# witch-dekatron1.net
KiCad netlist of a schematic drawn in EAGLE
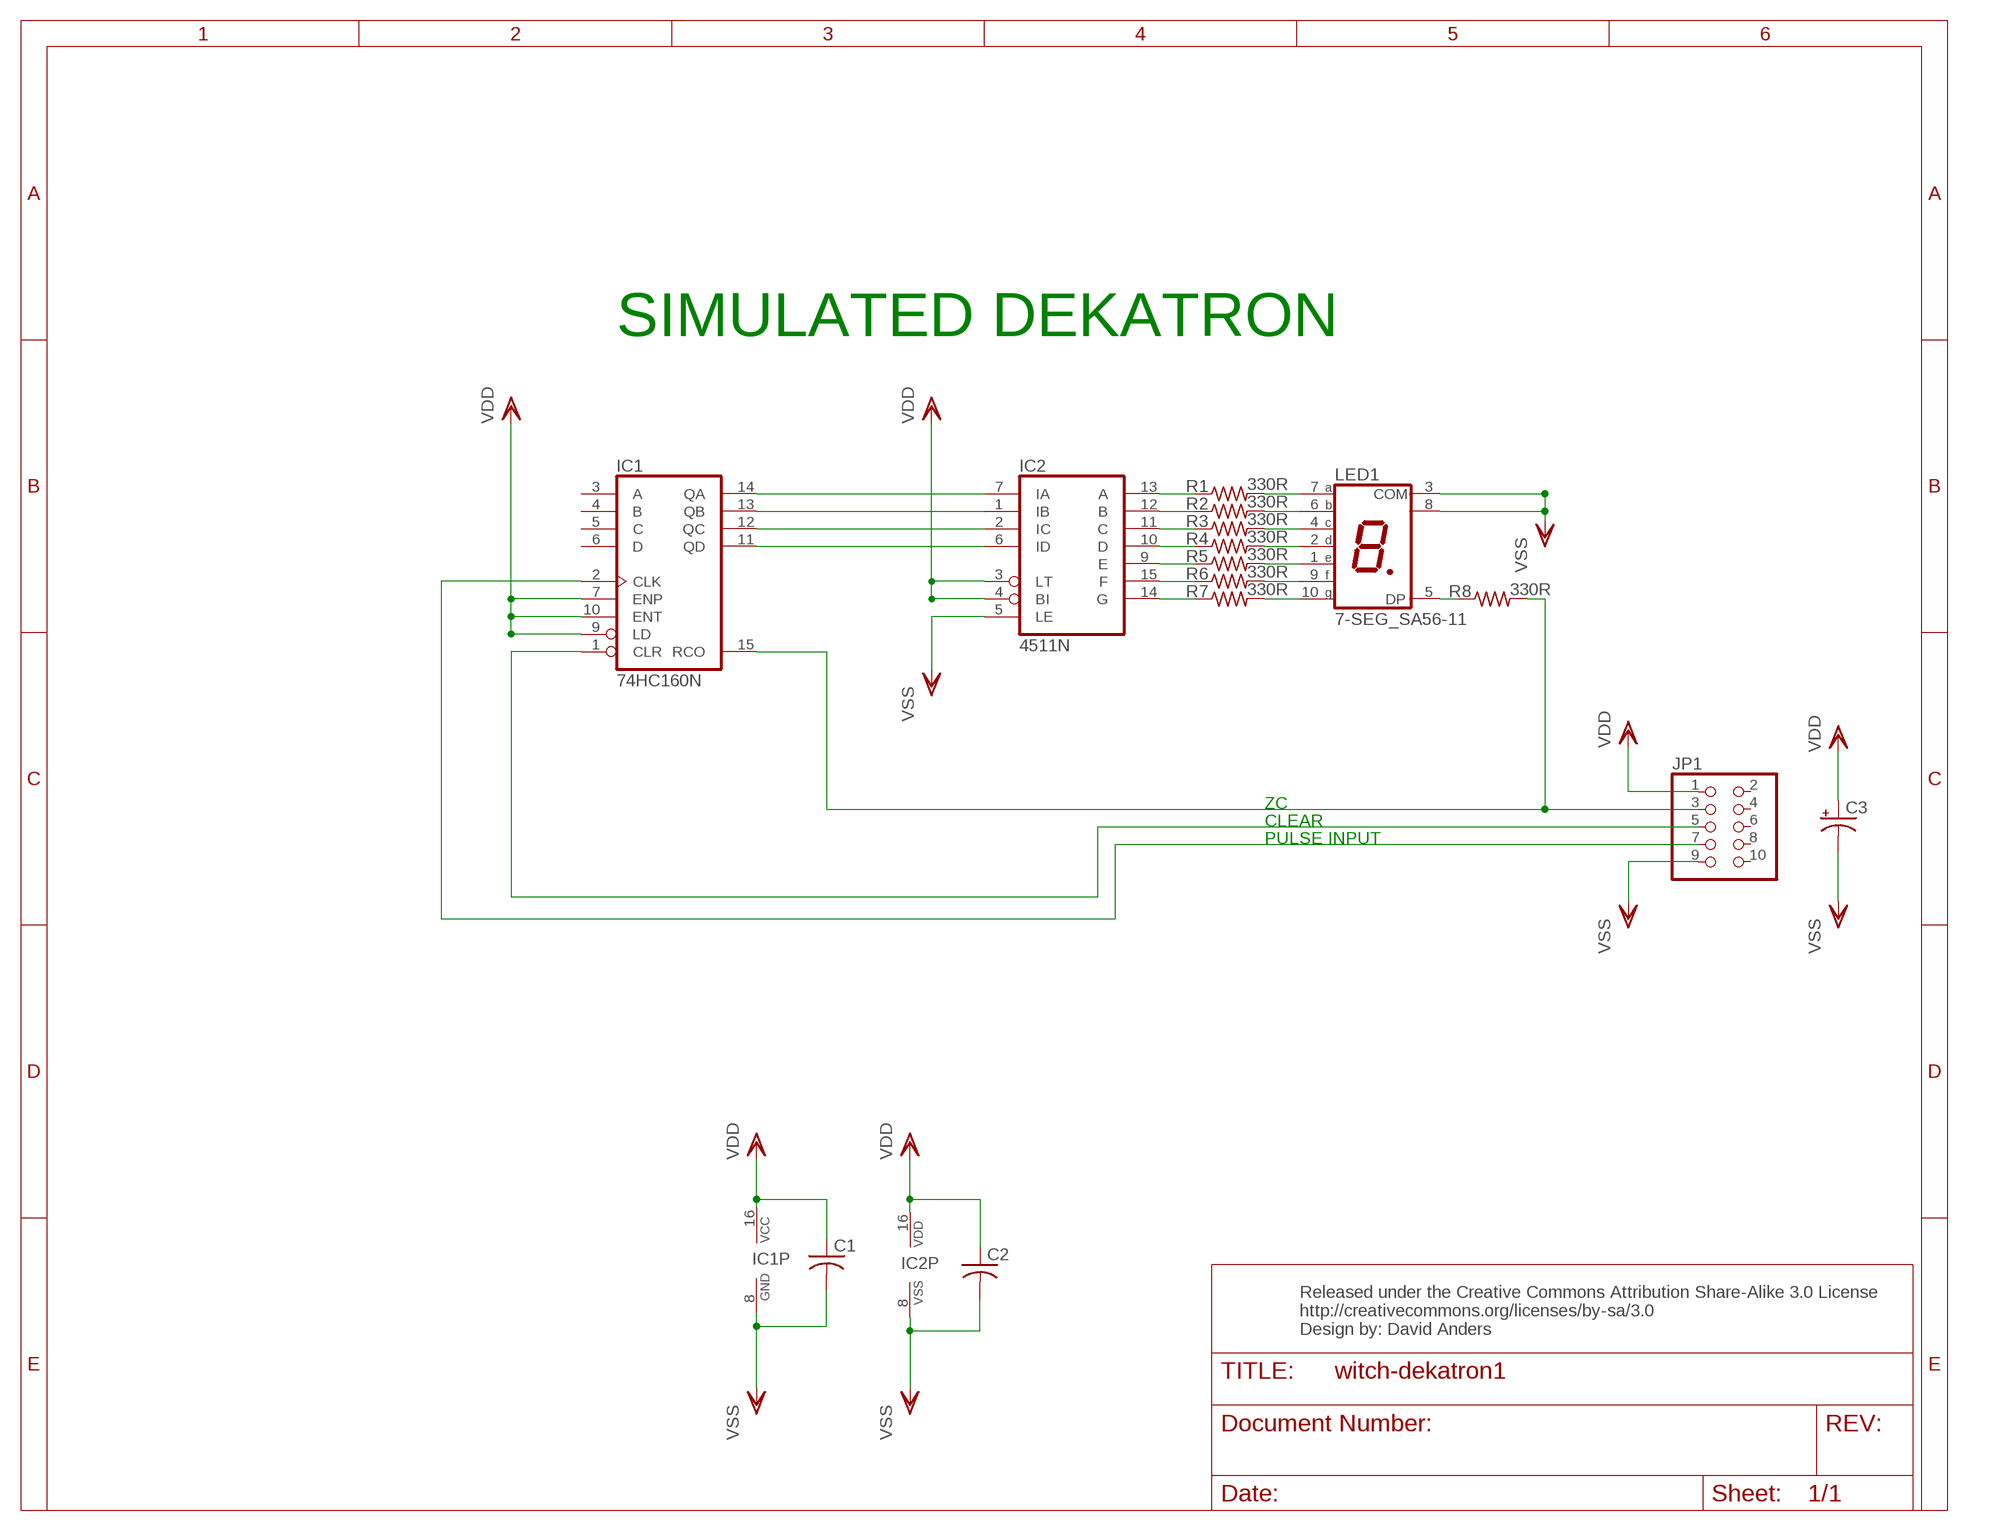
[diagram p0: schematic, sheet 1]

(export (version "E")
  (design (tool "Eeschema 10.0.6"))
  (components
    (comp (ref "C1")
      (value "C-US025-025X050")
      (footprint "eagle-import:C025-025X050")
      (libsource (lib "eagle-import") (part "C-US025-025X050"))
    )
    (comp (ref "C2")
      (value "C-US025-025X050")
      (footprint "eagle-import:C025-025X050")
      (libsource (lib "eagle-import") (part "C-US025-025X050"))
    )
    (comp (ref "C3")
      (value "CPOL-USE2-5")
      (footprint "eagle-import:E2-5")
      (libsource (lib "eagle-import") (part "CPOL-USE2-5"))
    )
    (comp (ref "IC1")
      (value "74HC160N")
      (footprint "eagle-import:DIL16")
      (libsource (lib "eagle-import") (part "74160NHC"))
    )
    (comp (ref "IC2")
      (value "4511N")
      (footprint "eagle-import:DIL16")
      (libsource (lib "eagle-import") (part "4511N"))
    )
    (comp (ref "JP1")
      (value "PINHD-2X5")
      (footprint "eagle-import:2X05")
      (libsource (lib "eagle-import") (part "PINHD-2X5"))
    )
    (comp (ref "LED1")
      (value "7-SEG_SA56-11")
      (footprint "eagle-import:SA56-11")
      (libsource (lib "eagle-import") (part "7-SEG_SA56-11"))
    )
    (comp (ref "R1")
      (value "330R")
      (footprint "eagle-import:0204_5")
      (libsource (lib "eagle-import") (part "R-US_0204/5"))
    )
    (comp (ref "R2")
      (value "330R")
      (footprint "eagle-import:0204_5")
      (libsource (lib "eagle-import") (part "R-US_0204/5"))
    )
    (comp (ref "R3")
      (value "330R")
      (footprint "eagle-import:0204_5")
      (libsource (lib "eagle-import") (part "R-US_0204/5"))
    )
    (comp (ref "R4")
      (value "330R")
      (footprint "eagle-import:0204_5")
      (libsource (lib "eagle-import") (part "R-US_0204/5"))
    )
    (comp (ref "R5")
      (value "330R")
      (footprint "eagle-import:0204_5")
      (libsource (lib "eagle-import") (part "R-US_0204/5"))
    )
    (comp (ref "R6")
      (value "330R")
      (footprint "eagle-import:0204_5")
      (libsource (lib "eagle-import") (part "R-US_0204/5"))
    )
    (comp (ref "R7")
      (value "330R")
      (footprint "eagle-import:0204_5")
      (libsource (lib "eagle-import") (part "R-US_0204/5"))
    )
    (comp (ref "R8")
      (value "330R")
      (footprint "eagle-import:0204_5")
      (libsource (lib "eagle-import") (part "R-US_0204/5"))
    )
  )
  (nets
    (net (code "1") (name "Net-(IC1A-CLK)") (class "Default")
      (node (ref "IC1") (pin "2") (pinfunction "CLK_2") (pintype "input"))
      (node (ref "JP1") (pin "7") (pinfunction "7_7") (pintype "passive"))
    )
    (net (code "2") (name "Net-(IC1A-CLR)") (class "Default")
      (node (ref "IC1") (pin "1") (pinfunction "CLR_1") (pintype "input"))
      (node (ref "JP1") (pin "5") (pinfunction "5_5") (pintype "passive"))
    )
    (net (code "3") (name "Net-(IC1A-QA)") (class "Default")
      (node (ref "IC1") (pin "14") (pinfunction "QA_14") (pintype "output"))
      (node (ref "IC2") (pin "7") (pinfunction "IA_7") (pintype "input"))
    )
    (net (code "4") (name "Net-(IC1A-QB)") (class "Default")
      (node (ref "IC1") (pin "13") (pinfunction "QB_13") (pintype "output"))
      (node (ref "IC2") (pin "1") (pinfunction "IB_1") (pintype "input"))
    )
    (net (code "5") (name "Net-(IC1A-QC)") (class "Default")
      (node (ref "IC1") (pin "12") (pinfunction "QC_12") (pintype "output"))
      (node (ref "IC2") (pin "2") (pinfunction "IC_2") (pintype "input"))
    )
    (net (code "6") (name "Net-(IC1A-QD)") (class "Default")
      (node (ref "IC1") (pin "11") (pinfunction "QD_11") (pintype "output"))
      (node (ref "IC2") (pin "6") (pinfunction "ID_6") (pintype "input"))
    )
    (net (code "7") (name "Net-(IC1A-RCO)") (class "Default")
      (node (ref "IC1") (pin "15") (pinfunction "RCO_15") (pintype "output"))
      (node (ref "JP1") (pin "3") (pinfunction "3_3") (pintype "passive"))
      (node (ref "R8") (pin "2") (pinfunction "2_2") (pintype "passive"))
    )
    (net (code "8") (name "Net-(IC2A-A)") (class "Default")
      (node (ref "IC2") (pin "13") (pinfunction "A_13") (pintype "output"))
      (node (ref "R1") (pin "1") (pinfunction "1_1") (pintype "passive"))
    )
    (net (code "9") (name "Net-(IC2A-B)") (class "Default")
      (node (ref "IC2") (pin "12") (pinfunction "B_12") (pintype "output"))
      (node (ref "R2") (pin "1") (pinfunction "1_1") (pintype "passive"))
    )
    (net (code "10") (name "Net-(IC2A-C)") (class "Default")
      (node (ref "IC2") (pin "11") (pinfunction "C_11") (pintype "output"))
      (node (ref "R3") (pin "1") (pinfunction "1_1") (pintype "passive"))
    )
    (net (code "11") (name "Net-(IC2A-D)") (class "Default")
      (node (ref "IC2") (pin "10") (pinfunction "D_10") (pintype "output"))
      (node (ref "R4") (pin "1") (pinfunction "1_1") (pintype "passive"))
    )
    (net (code "12") (name "Net-(IC2A-E)") (class "Default")
      (node (ref "IC2") (pin "9") (pinfunction "E_9") (pintype "output"))
      (node (ref "R5") (pin "1") (pinfunction "1_1") (pintype "passive"))
    )
    (net (code "13") (name "Net-(IC2A-F)") (class "Default")
      (node (ref "IC2") (pin "15") (pinfunction "F_15") (pintype "output"))
      (node (ref "R6") (pin "1") (pinfunction "1_1") (pintype "passive"))
    )
    (net (code "14") (name "Net-(IC2A-G)") (class "Default")
      (node (ref "IC2") (pin "14") (pinfunction "G_14") (pintype "output"))
      (node (ref "R7") (pin "1") (pinfunction "1_1") (pintype "passive"))
    )
    (net (code "15") (name "Net-(LED1-A)") (class "Default")
      (node (ref "LED1") (pin "7") (pinfunction "A_7") (pintype "passive"))
      (node (ref "R1") (pin "2") (pinfunction "2_2") (pintype "passive"))
    )
    (net (code "16") (name "Net-(LED1-B)") (class "Default")
      (node (ref "LED1") (pin "6") (pinfunction "B_6") (pintype "passive"))
      (node (ref "R2") (pin "2") (pinfunction "2_2") (pintype "passive"))
    )
    (net (code "17") (name "Net-(LED1-C)") (class "Default")
      (node (ref "LED1") (pin "4") (pinfunction "C_4") (pintype "passive"))
      (node (ref "R3") (pin "2") (pinfunction "2_2") (pintype "passive"))
    )
    (net (code "18") (name "Net-(LED1-D)") (class "Default")
      (node (ref "LED1") (pin "2") (pinfunction "D_2") (pintype "passive"))
      (node (ref "R4") (pin "2") (pinfunction "2_2") (pintype "passive"))
    )
    (net (code "19") (name "Net-(LED1-DP)") (class "Default")
      (node (ref "LED1") (pin "5") (pinfunction "DP_5") (pintype "passive"))
      (node (ref "R8") (pin "1") (pinfunction "1_1") (pintype "passive"))
    )
    (net (code "20") (name "Net-(LED1-E)") (class "Default")
      (node (ref "LED1") (pin "1") (pinfunction "E_1") (pintype "passive"))
      (node (ref "R5") (pin "2") (pinfunction "2_2") (pintype "passive"))
    )
    (net (code "21") (name "Net-(LED1-F)") (class "Default")
      (node (ref "LED1") (pin "9") (pinfunction "F_9") (pintype "passive"))
      (node (ref "R6") (pin "2") (pinfunction "2_2") (pintype "passive"))
    )
    (net (code "22") (name "Net-(LED1-G)") (class "Default")
      (node (ref "LED1") (pin "10") (pinfunction "G_10") (pintype "passive"))
      (node (ref "R7") (pin "2") (pinfunction "2_2") (pintype "passive"))
    )
    (net (code "23") (name "VDD") (class "Default")
      (node (ref "C1") (pin "1") (pinfunction "1_1") (pintype "passive"))
      (node (ref "C2") (pin "1") (pinfunction "1_1") (pintype "passive"))
      (node (ref "C3") (pin "+") (pinfunction "+_+") (pintype "passive"))
      (node (ref "IC1") (pin "10") (pinfunction "ENT_10") (pintype "input"))
      (node (ref "IC1") (pin "16") (pinfunction "VCC_16") (pintype "power_in"))
      (node (ref "IC1") (pin "7") (pinfunction "ENP_7") (pintype "input"))
      (node (ref "IC1") (pin "9") (pinfunction "LD_9") (pintype "input"))
      (node (ref "IC2") (pin "16") (pinfunction "VDD_16") (pintype "power_in"))
      (node (ref "IC2") (pin "3") (pinfunction "LT_3") (pintype "input"))
      (node (ref "IC2") (pin "4") (pinfunction "BI_4") (pintype "input"))
      (node (ref "JP1") (pin "1") (pinfunction "1_1") (pintype "passive"))
    )
    (net (code "24") (name "VSS") (class "Default")
      (node (ref "C1") (pin "2") (pinfunction "2_2") (pintype "passive"))
      (node (ref "C2") (pin "2") (pinfunction "2_2") (pintype "passive"))
      (node (ref "C3") (pin "-") (pinfunction "-_-") (pintype "passive"))
      (node (ref "IC1") (pin "8") (pinfunction "GND_8") (pintype "power_in"))
      (node (ref "IC2") (pin "5") (pinfunction "LE_5") (pintype "input"))
      (node (ref "IC2") (pin "8") (pinfunction "VSS_8") (pintype "power_in"))
      (node (ref "JP1") (pin "9") (pinfunction "9_9") (pintype "passive"))
      (node (ref "LED1") (pin "3") (pinfunction "COM_3") (pintype "passive"))
      (node (ref "LED1") (pin "8") (pinfunction "COM_8") (pintype "passive"))
    )
    (net (code "25") (name "unconnected-(IC1A-A-Pad3)") (class "Default")
      (node (ref "IC1") (pin "3") (pinfunction "A_3") (pintype "input"))
    )
    (net (code "26") (name "unconnected-(IC1A-B-Pad4)") (class "Default")
      (node (ref "IC1") (pin "4") (pinfunction "B_4") (pintype "input"))
    )
    (net (code "27") (name "unconnected-(IC1A-C-Pad5)") (class "Default")
      (node (ref "IC1") (pin "5") (pinfunction "C_5") (pintype "input"))
    )
    (net (code "28") (name "unconnected-(IC1A-D-Pad6)") (class "Default")
      (node (ref "IC1") (pin "6") (pinfunction "D_6") (pintype "input"))
    )
    (net (code "29") (name "unconnected-(JP1-Pad2)") (class "Default")
      (node (ref "JP1") (pin "2") (pinfunction "2_2") (pintype "passive"))
    )
    (net (code "30") (name "unconnected-(JP1-Pad4)") (class "Default")
      (node (ref "JP1") (pin "4") (pinfunction "4_4") (pintype "passive"))
    )
    (net (code "31") (name "unconnected-(JP1-Pad6)") (class "Default")
      (node (ref "JP1") (pin "6") (pinfunction "6_6") (pintype "passive"))
    )
    (net (code "32") (name "unconnected-(JP1-Pad8)") (class "Default")
      (node (ref "JP1") (pin "8") (pinfunction "8_8") (pintype "passive"))
    )
    (net (code "33") (name "unconnected-(JP1-Pad10)") (class "Default")
      (node (ref "JP1") (pin "10") (pinfunction "10_10") (pintype "passive"))
    )
  )
)
